# Power_5V.net
KiCad netlist of a schematic drawn in Altium Designer
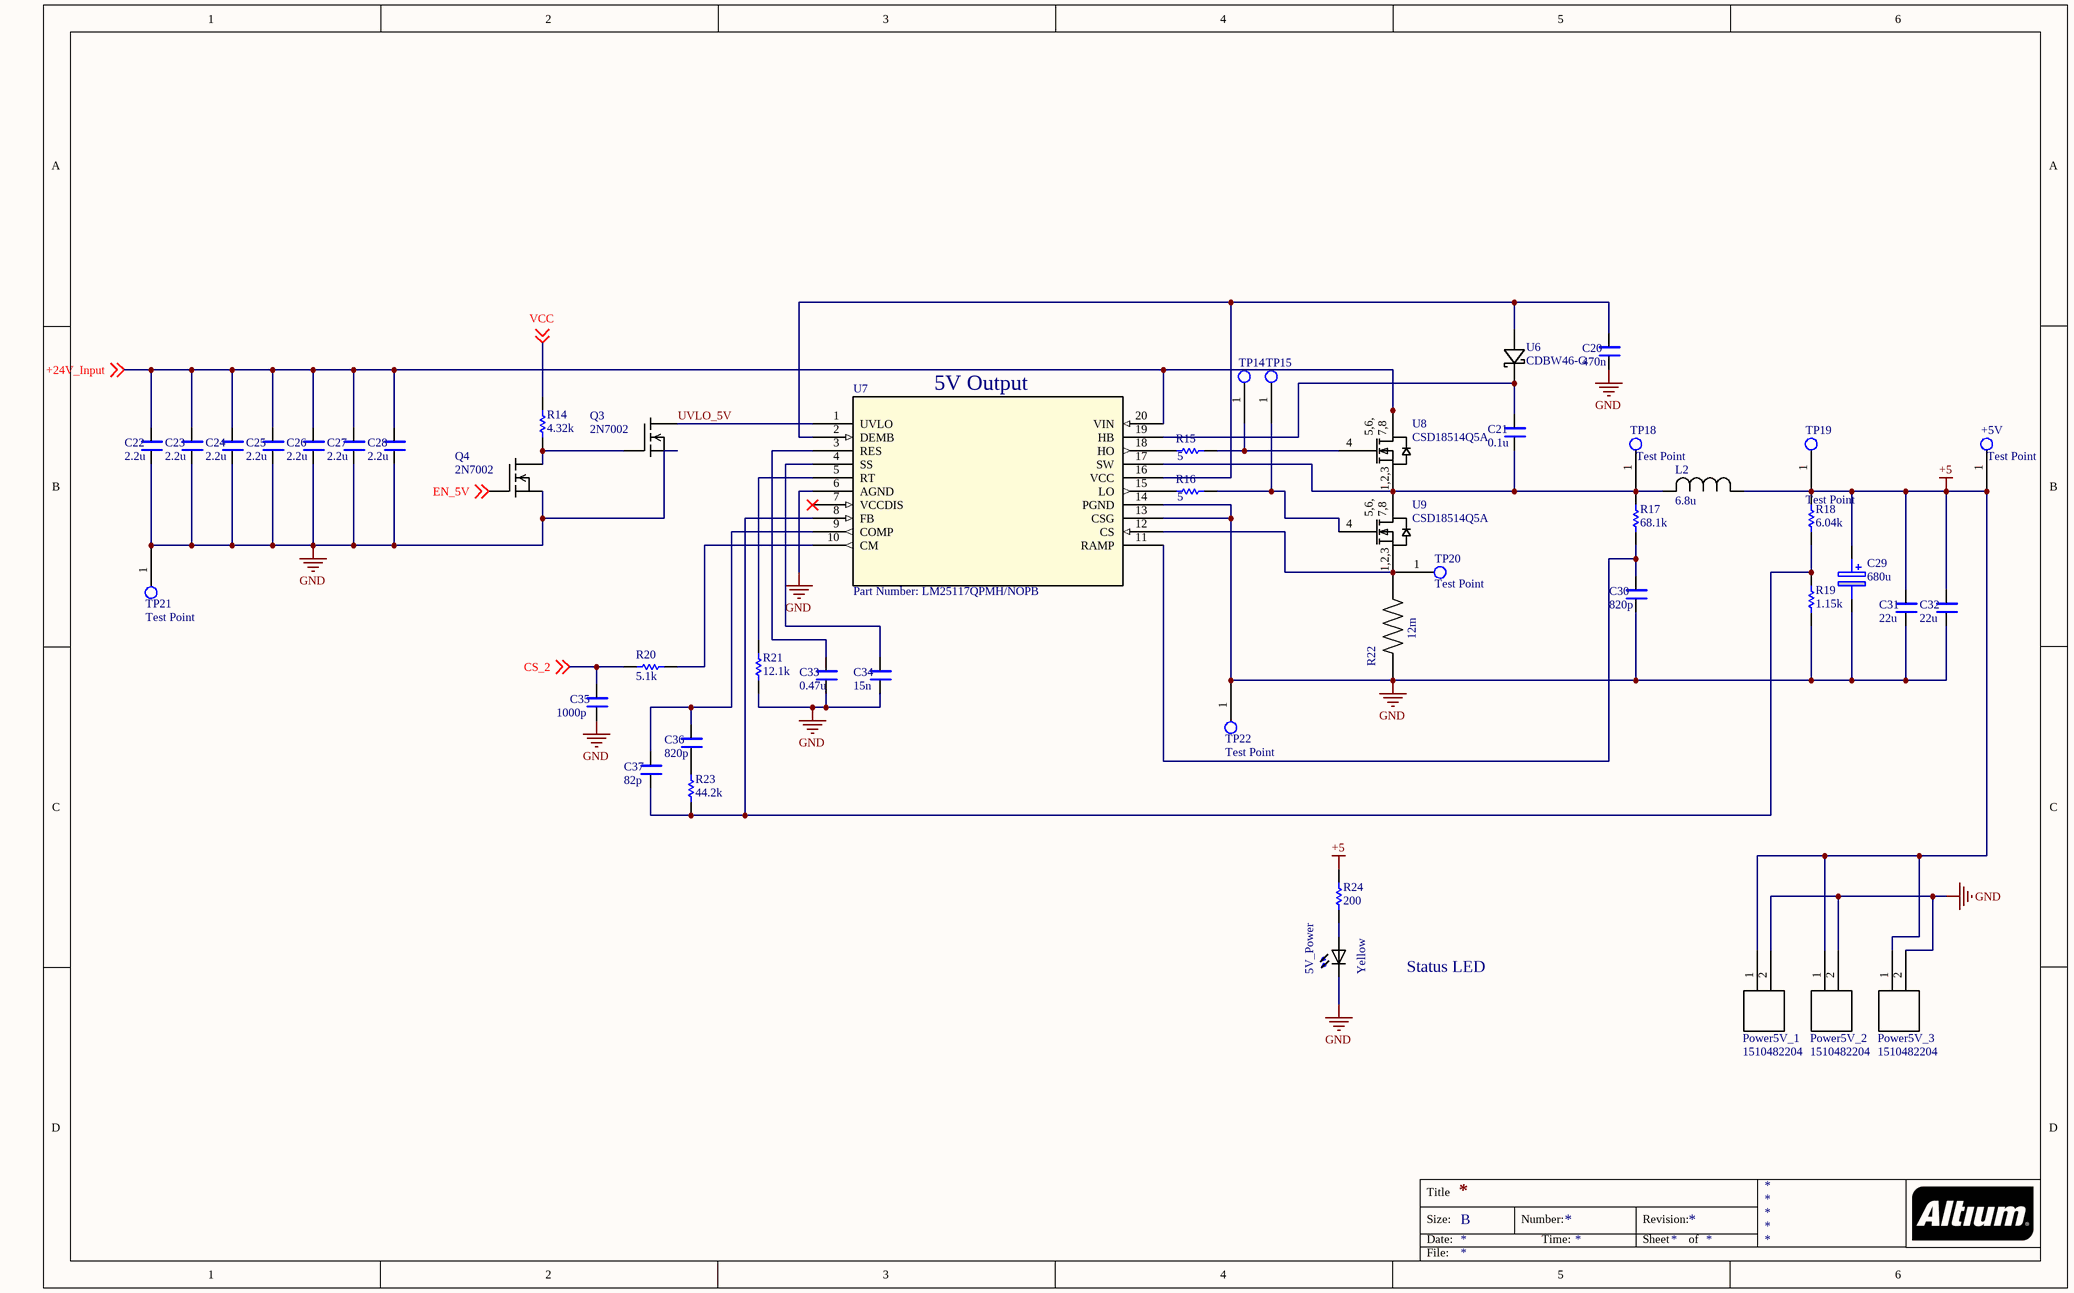
[diagram p0: Power_5V.SchDoc]

(export (version "E")
  (design (tool "Eeschema 10.0.6"))
  (components
    (comp (ref "+5V")
      (value "Test Point")
      (footprint "Test Point Through-hole")
      (libsource (lib "Test Points") (part "Test Point"))
    )
    (comp (ref "5V_Power")
      (value "Yellow")
      (footprint "*DIOC200X125X110_LTST-C171KSKT(Primary)")
      (description "Yellow 2 x 1.25 x 0.8 mm 130Â° Water Clear 50 mcd 2 V LED SMT")
      (fields (field (name "MP") "LTST-C171KSKT") (field (name "DIGI-KEY_PART_NUMBER") "160-1428-1-ND"))
      (libsource (lib "LTST-C171KSKT") (part "LTST-C171KSKT"))
    )
    (comp (ref "C20")
      (value "470n")
      (footprint "*CAPC2012X88N")
      (description "100pF Â±5% 250V Ceramic Capacitor C0G, NP0 0805 _2012 Metric_")
      (fields (field (name "MF") "KEMET") (field (name "DIGI-KEY_PART_NUMBER") "399-15000-1-ND"))
      (libsource (lib "C0805C101JAGAC7800") (part "C0805C101JAGAC7800"))
    )
    (comp (ref "C21")
      (value "0.1u")
      (footprint "*CAPC2012X88N")
      (description "100pF Â±5% 250V Ceramic Capacitor C0G, NP0 0805 _2012 Metric_")
      (fields (field (name "MF") "KEMET") (field (name "DIGI-KEY_PART_NUMBER") "399-15000-1-ND"))
      (libsource (lib "C0805C101JAGAC7800") (part "C0805C101JAGAC7800"))
    )
    (comp (ref "C22")
      (value "2.2u")
      (footprint "*CAPC2012X88N")
      (description "100pF Â±5% 250V Ceramic Capacitor C0G, NP0 0805 _2012 Metric_")
      (fields (field (name "MF") "KEMET") (field (name "DIGI-KEY_PART_NUMBER") "399-15000-1-ND"))
      (libsource (lib "C0805C101JAGAC7800") (part "C0805C101JAGAC7800"))
    )
    (comp (ref "C23")
      (value "2.2u")
      (footprint "*CAPC2012X88N")
      (description "100pF Â±5% 250V Ceramic Capacitor C0G, NP0 0805 _2012 Metric_")
      (fields (field (name "MF") "KEMET") (field (name "DIGI-KEY_PART_NUMBER") "399-15000-1-ND"))
      (libsource (lib "C0805C101JAGAC7800") (part "C0805C101JAGAC7800"))
    )
    (comp (ref "C24")
      (value "2.2u")
      (footprint "*CAPC2012X88N")
      (description "100pF Â±5% 250V Ceramic Capacitor C0G, NP0 0805 _2012 Metric_")
      (fields (field (name "MF") "KEMET") (field (name "DIGI-KEY_PART_NUMBER") "399-15000-1-ND"))
      (libsource (lib "C0805C101JAGAC7800") (part "C0805C101JAGAC7800"))
    )
    (comp (ref "C25")
      (value "2.2u")
      (footprint "*CAPC2012X88N")
      (description "100pF Â±5% 250V Ceramic Capacitor C0G, NP0 0805 _2012 Metric_")
      (fields (field (name "MF") "KEMET") (field (name "DIGI-KEY_PART_NUMBER") "399-15000-1-ND"))
      (libsource (lib "C0805C101JAGAC7800") (part "C0805C101JAGAC7800"))
    )
    (comp (ref "C26")
      (value "2.2u")
      (footprint "*CAPC2012X88N")
      (description "100pF Â±5% 250V Ceramic Capacitor C0G, NP0 0805 _2012 Metric_")
      (fields (field (name "MF") "KEMET") (field (name "DIGI-KEY_PART_NUMBER") "399-15000-1-ND"))
      (libsource (lib "C0805C101JAGAC7800") (part "C0805C101JAGAC7800"))
    )
    (comp (ref "C27")
      (value "2.2u")
      (footprint "*CAPC2012X88N")
      (description "100pF Â±5% 250V Ceramic Capacitor C0G, NP0 0805 _2012 Metric_")
      (fields (field (name "MF") "KEMET") (field (name "DIGI-KEY_PART_NUMBER") "399-15000-1-ND"))
      (libsource (lib "C0805C101JAGAC7800") (part "C0805C101JAGAC7800"))
    )
    (comp (ref "C28")
      (value "2.2u")
      (footprint "*CAPC2012X88N")
      (description "100pF Â±5% 250V Ceramic Capacitor C0G, NP0 0805 _2012 Metric_")
      (fields (field (name "MF") "KEMET") (field (name "DIGI-KEY_PART_NUMBER") "399-15000-1-ND"))
      (libsource (lib "C0805C101JAGAC7800") (part "C0805C101JAGAC7800"))
    )
    (comp (ref "C29")
      (value "680u")
      (footprint "CAPPRD500W65D1000H1800")
      (fields
        (field (name "MANUFACTURER_PART_NUMBER") "EEUFC1V331")
        (field (name "RS PART NUMBER") "1081337")
      )
      (libsource (lib "Power Distribution") (part "EEUFC1V331"))
    )
    (comp (ref "C30")
      (value "820p")
      (footprint "*CAPC2012X88N")
      (description "100pF Â±5% 250V Ceramic Capacitor C0G, NP0 0805 _2012 Metric_")
      (fields (field (name "MF") "KEMET") (field (name "DIGI-KEY_PART_NUMBER") "399-15000-1-ND"))
      (libsource (lib "C0805C101JAGAC7800") (part "C0805C101JAGAC7800"))
    )
    (comp (ref "C31")
      (value "22u")
      (footprint "*CAPC2012X88N")
      (description "100pF Â±5% 250V Ceramic Capacitor C0G, NP0 0805 _2012 Metric_")
      (fields (field (name "MF") "KEMET") (field (name "DIGI-KEY_PART_NUMBER") "399-15000-1-ND"))
      (libsource (lib "C0805C101JAGAC7800") (part "C0805C101JAGAC7800"))
    )
    (comp (ref "C32")
      (value "22u")
      (footprint "*CAPC2012X88N")
      (description "100pF Â±5% 250V Ceramic Capacitor C0G, NP0 0805 _2012 Metric_")
      (fields (field (name "MF") "KEMET") (field (name "DIGI-KEY_PART_NUMBER") "399-15000-1-ND"))
      (libsource (lib "C0805C101JAGAC7800") (part "C0805C101JAGAC7800"))
    )
    (comp (ref "C33")
      (value "0.47u")
      (footprint "*CAPC2012X88N")
      (description "100pF Â±5% 250V Ceramic Capacitor C0G, NP0 0805 _2012 Metric_")
      (fields (field (name "MF") "KEMET") (field (name "DIGI-KEY_PART_NUMBER") "399-15000-1-ND"))
      (libsource (lib "C0805C101JAGAC7800") (part "C0805C101JAGAC7800"))
    )
    (comp (ref "C34")
      (value "15n")
      (footprint "*CAPC2012X88N")
      (description "100pF Â±5% 250V Ceramic Capacitor C0G, NP0 0805 _2012 Metric_")
      (fields (field (name "MF") "KEMET") (field (name "DIGI-KEY_PART_NUMBER") "399-15000-1-ND"))
      (libsource (lib "C0805C101JAGAC7800") (part "C0805C101JAGAC7800"))
    )
    (comp (ref "C35")
      (value "1000p")
      (footprint "*CAPC2012X88N")
      (description "100pF Â±5% 250V Ceramic Capacitor C0G, NP0 0805 _2012 Metric_")
      (fields (field (name "MF") "KEMET") (field (name "DIGI-KEY_PART_NUMBER") "399-15000-1-ND"))
      (libsource (lib "C0805C101JAGAC7800") (part "C0805C101JAGAC7800"))
    )
    (comp (ref "C36")
      (value "820p")
      (footprint "*CAPC2012X88N")
      (description "100pF Â±5% 250V Ceramic Capacitor C0G, NP0 0805 _2012 Metric_")
      (fields (field (name "MF") "KEMET") (field (name "DIGI-KEY_PART_NUMBER") "399-15000-1-ND"))
      (libsource (lib "C0805C101JAGAC7800") (part "C0805C101JAGAC7800"))
    )
    (comp (ref "C37")
      (value "82p")
      (footprint "*CAPC2012X88N")
      (description "100pF Â±5% 250V Ceramic Capacitor C0G, NP0 0805 _2012 Metric_")
      (fields (field (name "MF") "KEMET") (field (name "DIGI-KEY_PART_NUMBER") "399-15000-1-ND"))
      (libsource (lib "C0805C101JAGAC7800") (part "C0805C101JAGAC7800"))
    )
    (comp (ref "L2")
      (value "6.8u")
      (footprint "IND_BOURNS_SRP12")
      (description "No Description Available")
      (fields
        (field (name "MANUFACTURER_PART_NUMBER") "SRP1270-6R8M")
        (field (name "COPYRIGHT") "Copyright (C) 2018 Accelerated Designs. All rights reserved")
      )
      (libsource (lib "Inductor") (part "SRP1270-6R8M"))
    )
    (comp (ref "Power5V_1")
      (value "1510482204")
      (footprint "1510482204")
      (description "Molex 6.5MM 2 pin connector, used for power connections. P/N 1510482204 and similar models.")
      (libsource (lib "Power Distribution") (part "1510482204"))
    )
    (comp (ref "Power5V_2")
      (value "1510482204")
      (footprint "1510482204")
      (description "Molex 6.5MM 2 pin connector, used for power connections. P/N 1510482204 and similar models.")
      (libsource (lib "Power Distribution") (part "1510482204"))
    )
    (comp (ref "Power5V_3")
      (value "1510482204")
      (footprint "1510482204")
      (description "Molex 6.5MM 2 pin connector, used for power connections. P/N 1510482204 and similar models.")
      (libsource (lib "Power Distribution") (part "1510482204"))
    )
    (comp (ref "Q3")
      (value "2N7002")
      (footprint "*SOT23")
      (description "Trans MOSFET N-CH 60V 0.115A 3-Pin SOT-23 T/R")
      (fields (field (name "MF") "ON Semiconductor"))
      (libsource (lib "2N7002") (part "2N7002"))
    )
    (comp (ref "Q4")
      (value "2N7002")
      (footprint "*SOT23")
      (description "Trans MOSFET N-CH 60V 0.115A 3-Pin SOT-23 T/R")
      (fields (field (name "MF") "ON Semiconductor"))
      (libsource (lib "2N7002") (part "2N7002"))
    )
    (comp (ref "R14")
      (value "4.32k")
      (footprint "RESC0805(2012)_M")
      (description "8M06 0.125W 1% 0805 (2012 Metric)  SMD")
      (fields (field (name "POWER") "0.125 W") (field (name "TOLERANCE") "1 %"))
      (libsource (lib "Altium Content Vault") (part "RES"))
    )
    (comp (ref "R15")
      (value "5")
      (footprint "AXIAL-0.3")
      (description "120R 0.125W 5% 0805 (2012 Metric)  SMD")
      (fields (field (name "TOLERANCE") "5 %") (field (name "POWER") "0.125 W"))
      (libsource (lib "Power Distribution") (part "120R 5% 0805"))
    )
    (comp (ref "R16")
      (value "5")
      (footprint "AXIAL-0.3")
      (description "120R 0.125W 5% 0805 (2012 Metric)  SMD")
      (fields (field (name "TOLERANCE") "5 %") (field (name "POWER") "0.125 W"))
      (libsource (lib "Power Distribution") (part "120R 5% 0805"))
    )
    (comp (ref "R17")
      (value "68.1k")
      (footprint "RESC0805(2012)_M")
      (description "8M06 0.125W 1% 0805 (2012 Metric)  SMD")
      (fields (field (name "POWER") "0.125 W") (field (name "TOLERANCE") "1 %"))
      (libsource (lib "Altium Content Vault") (part "RES"))
    )
    (comp (ref "R18")
      (value "6.04k")
      (footprint "RESC0805(2012)_M")
      (description "8M06 0.125W 1% 0805 (2012 Metric)  SMD")
      (fields (field (name "POWER") "0.125 W") (field (name "TOLERANCE") "1 %"))
      (libsource (lib "Altium Content Vault") (part "RES"))
    )
    (comp (ref "R19")
      (value "1.15k")
      (footprint "RESC0805(2012)_M")
      (description "8M06 0.125W 1% 0805 (2012 Metric)  SMD")
      (fields (field (name "POWER") "0.125 W") (field (name "TOLERANCE") "1 %"))
      (libsource (lib "Altium Content Vault") (part "RES"))
    )
    (comp (ref "R20")
      (value "5.1k")
      (footprint "RESC0805(2012)_M")
      (description "8M06 0.125W 1% 0805 (2012 Metric)  SMD")
      (fields (field (name "POWER") "0.125 W") (field (name "TOLERANCE") "1 %"))
      (libsource (lib "Altium Content Vault") (part "RES"))
    )
    (comp (ref "R21")
      (value "12.1k")
      (footprint "RESC0805(2012)_M")
      (description "8M06 0.125W 1% 0805 (2012 Metric)  SMD")
      (fields (field (name "POWER") "0.125 W") (field (name "TOLERANCE") "1 %"))
      (libsource (lib "Altium Content Vault") (part "RES"))
    )
    (comp (ref "R22")
      (value "12m")
      (footprint "*RESC6432X110N")
      (description "Res Thick Film 2512 0.012 Ohm 1% 1W Pad SMD Automotive T/R")
      (fields (field (name "MP") "ERJ-M1WSF12MU") (field (name "DIGI-KEY_PART_NUMBER") "P12MCT-ND"))
      (libsource (lib "ERJ-M1WSF12MU") (part "ERJ-M1WSF12MU"))
    )
    (comp (ref "R23")
      (value "44.2k")
      (footprint "RESC0805(2012)_M")
      (description "8M06 0.125W 1% 0805 (2012 Metric)  SMD")
      (fields (field (name "POWER") "0.125 W") (field (name "TOLERANCE") "1 %"))
      (libsource (lib "Altium Content Vault") (part "RES"))
    )
    (comp (ref "R24")
      (value "200")
      (footprint "RESC0805(2012)_M")
      (description "8M06 0.125W 1% 0805 (2012 Metric)  SMD")
      (fields (field (name "POWER") "0.125 W") (field (name "TOLERANCE") "1 %"))
      (libsource (lib "Altium Content Vault") (part "RES"))
    )
    (comp (ref "TP14")
      (value "~")
      (footprint "Test Point Through-hole")
      (libsource (lib "Test Points") (part "Test Point"))
    )
    (comp (ref "TP15")
      (value "~")
      (footprint "Test Point Through-hole")
      (libsource (lib "Test Points") (part "Test Point"))
    )
    (comp (ref "TP18")
      (value "Test Point")
      (footprint "Test Point Through-hole")
      (libsource (lib "Test Points") (part "Test Point"))
    )
    (comp (ref "TP19")
      (value "Test Point")
      (footprint "Test Point Through-hole")
      (libsource (lib "Test Points") (part "Test Point"))
    )
    (comp (ref "TP20")
      (value "Test Point")
      (footprint "Test Point Through-hole")
      (libsource (lib "Test Points") (part "Test Point"))
    )
    (comp (ref "TP21")
      (value "Test Point")
      (footprint "Test Point Through-hole")
      (libsource (lib "Test Points") (part "Test Point"))
    )
    (comp (ref "TP22")
      (value "Test Point")
      (footprint "Test Point Through-hole")
      (libsource (lib "Test Points") (part "Test Point"))
    )
    (comp (ref "U6")
      (value "CDBW46-G")
      (footprint "CDBW")
      (description "No Description Available")
      (fields (field (name "COPYRIGHT") "Copyright (C) 2018 Accelerated Designs. All rights reserved"))
      (libsource (lib "DIODE SCHOTTKY 100V 150MA") (part "CDBW46-G"))
    )
    (comp (ref "U7")
      (value "Part Number: LM25117QPMH/NOPB")
      (footprint "MXA20A")
      (description "No Description Available")
      (fields
        (field (name "MANUFACTURER") "Texas Instruments")
        (field (name "MANUFACTURER_PART_NUMBER") "LM25117QPMH/NOPB")
        (field (name "COPYRIGHT") "Copyright (C) 2018 Accelerated Designs. All rights reserved")
      )
      (libsource (lib "2019-11-16_22-35-15") (part "LM25117QPMH/NOPB"))
    )
    (comp (ref "U8")
      (value "CSD18514Q5A")
      (footprint "DQJ0008A")
      (description "No Description Available")
      (fields (field (name "COPYRIGHT") "Copyright (C) 2018 Accelerated Designs. All rights reserved"))
      (libsource (lib "ul_CSD18514Q5A") (part "CSD18514Q5A"))
    )
    (comp (ref "U9")
      (value "CSD18514Q5A")
      (footprint "DQJ0008A")
      (description "No Description Available")
      (fields (field (name "COPYRIGHT") "Copyright (C) 2018 Accelerated Designs. All rights reserved"))
      (libsource (lib "ul_CSD18514Q5A") (part "CSD18514Q5A"))
    )
  )
  (nets
    (net (code "1") (name "+5") (class "Default")
      (node (ref "+5V") (pin "1") (pinfunction "1_1") (pintype "passive"))
      (node (ref "C29") (pin "1") (pinfunction "+_1") (pintype "passive"))
      (node (ref "C31") (pin "2") (pinfunction "2_2") (pintype "passive"))
      (node (ref "C32") (pin "2") (pinfunction "2_2") (pintype "passive"))
      (node (ref "L2") (pin "1") (pinfunction "1_1") (pintype "passive"))
      (node (ref "Power5V_1") (pin "1") (pintype "passive"))
      (node (ref "Power5V_2") (pin "1") (pintype "passive"))
      (node (ref "Power5V_3") (pin "1") (pintype "passive"))
      (node (ref "R18") (pin "2") (pinfunction "2_2") (pintype "passive"))
      (node (ref "R24") (pin "2") (pinfunction "2_2") (pintype "passive"))
      (node (ref "TP19") (pin "1") (pinfunction "1_1") (pintype "passive"))
    )
    (net (code "2") (name "+24V_Input") (class "Default")
      (node (ref "C22") (pin "2") (pinfunction "2_2") (pintype "passive"))
      (node (ref "C23") (pin "2") (pinfunction "2_2") (pintype "passive"))
      (node (ref "C24") (pin "2") (pinfunction "2_2") (pintype "passive"))
      (node (ref "C25") (pin "2") (pinfunction "2_2") (pintype "passive"))
      (node (ref "C26") (pin "2") (pinfunction "2_2") (pintype "passive"))
      (node (ref "C27") (pin "2") (pinfunction "2_2") (pintype "passive"))
      (node (ref "C28") (pin "2") (pinfunction "2_2") (pintype "passive"))
      (node (ref "U7") (pin "20") (pinfunction "VIN_20") (pintype "input"))
      (node (ref "U8") (pin "5") (pinfunction "D_5") (pintype "passive"))
      (node (ref "U8") (pin "6") (pinfunction "D_6") (pintype "passive"))
      (node (ref "U8") (pin "7") (pinfunction "D_7") (pintype "passive"))
      (node (ref "U8") (pin "8") (pinfunction "D_8") (pintype "passive"))
    )
    (net (code "3") (name "/UVLO_5V") (class "Default")
      (node (ref "Q3") (pin "3") (pinfunction "D_3") (pintype "passive"))
      (node (ref "U7") (pin "1") (pinfunction "UVLO_1") (pintype "passive"))
    )
    (net (code "4") (name "CS_2") (class "Default")
      (node (ref "C35") (pin "2") (pinfunction "2_2") (pintype "passive"))
      (node (ref "R20") (pin "2") (pinfunction "2_2") (pintype "passive"))
    )
    (net (code "5") (name "EN_5V") (class "Default")
      (node (ref "Q4") (pin "1") (pinfunction "G_1") (pintype "passive"))
    )
    (net (code "6") (name "GND") (class "Default")
      (node (ref "5V_Power") (pin "NEG") (pinfunction "NEG_NEG") (pintype "passive"))
      (node (ref "C20") (pin "1") (pinfunction "1_1") (pintype "passive"))
      (node (ref "C22") (pin "1") (pinfunction "1_1") (pintype "passive"))
      (node (ref "C23") (pin "1") (pinfunction "1_1") (pintype "passive"))
      (node (ref "C24") (pin "1") (pinfunction "1_1") (pintype "passive"))
      (node (ref "C25") (pin "1") (pinfunction "1_1") (pintype "passive"))
      (node (ref "C26") (pin "1") (pinfunction "1_1") (pintype "passive"))
      (node (ref "C27") (pin "1") (pinfunction "1_1") (pintype "passive"))
      (node (ref "C28") (pin "1") (pinfunction "1_1") (pintype "passive"))
      (node (ref "C29") (pin "2") (pinfunction "-_2") (pintype "passive"))
      (node (ref "C30") (pin "1") (pinfunction "1_1") (pintype "passive"))
      (node (ref "C31") (pin "1") (pinfunction "1_1") (pintype "passive"))
      (node (ref "C32") (pin "1") (pinfunction "1_1") (pintype "passive"))
      (node (ref "C33") (pin "1") (pinfunction "1_1") (pintype "passive"))
      (node (ref "C34") (pin "1") (pinfunction "1_1") (pintype "passive"))
      (node (ref "C35") (pin "1") (pinfunction "1_1") (pintype "passive"))
      (node (ref "Power5V_1") (pin "2") (pintype "passive"))
      (node (ref "Power5V_2") (pin "2") (pintype "passive"))
      (node (ref "Power5V_3") (pin "2") (pintype "passive"))
      (node (ref "Q3") (pin "2") (pinfunction "S_2") (pintype "passive"))
      (node (ref "Q4") (pin "2") (pinfunction "S_2") (pintype "passive"))
      (node (ref "R19") (pin "1") (pinfunction "1_1") (pintype "passive"))
      (node (ref "R21") (pin "1") (pinfunction "1_1") (pintype "passive"))
      (node (ref "R22") (pin "1") (pinfunction "1_1") (pintype "passive"))
      (node (ref "TP21") (pin "1") (pinfunction "1_1") (pintype "passive"))
      (node (ref "TP22") (pin "1") (pinfunction "1_1") (pintype "passive"))
      (node (ref "U7") (pin "13") (pinfunction "CSG_13") (pintype "passive"))
      (node (ref "U7") (pin "14") (pinfunction "PGND_14") (pintype "power_in"))
      (node (ref "U7") (pin "6") (pinfunction "AGND_6") (pintype "power_in"))
    )
    (net (code "7") (name "Net-(5V_Power-PadPOS)") (class "Default")
      (node (ref "5V_Power") (pin "POS") (pinfunction "POS_POS") (pintype "passive"))
      (node (ref "R24") (pin "1") (pinfunction "1_1") (pintype "passive"))
    )
    (net (code "8") (name "Net-(C36-Pad1)") (class "Default")
      (node (ref "C36") (pin "1") (pinfunction "1_1") (pintype "passive"))
      (node (ref "R23") (pin "2") (pinfunction "2_2") (pintype "passive"))
    )
    (net (code "9") (name "Net-(Q3-G)") (class "Default")
      (node (ref "Q3") (pin "1") (pinfunction "G_1") (pintype "passive"))
      (node (ref "Q4") (pin "3") (pinfunction "D_3") (pintype "passive"))
      (node (ref "R14") (pin "1") (pinfunction "1_1") (pintype "passive"))
    )
    (net (code "10") (name "Net-(U7-CM)") (class "Default")
      (node (ref "R20") (pin "1") (pinfunction "1_1") (pintype "passive"))
      (node (ref "U7") (pin "10") (pinfunction "CM_10") (pintype "output"))
    )
    (net (code "11") (name "Net-(U7-COMP)") (class "Default")
      (node (ref "C36") (pin "2") (pinfunction "2_2") (pintype "passive"))
      (node (ref "C37") (pin "2") (pinfunction "2_2") (pintype "passive"))
      (node (ref "U7") (pin "9") (pinfunction "COMP_9") (pintype "output"))
    )
    (net (code "12") (name "Net-(U7-CS)") (class "Default")
      (node (ref "R22") (pin "2") (pinfunction "2_2") (pintype "passive"))
      (node (ref "TP20") (pin "1") (pinfunction "1_1") (pintype "passive"))
      (node (ref "U7") (pin "12") (pinfunction "CS_12") (pintype "input"))
      (node (ref "U9") (pin "1") (pinfunction "S_1") (pintype "passive"))
      (node (ref "U9") (pin "2") (pinfunction "S_2") (pintype "passive"))
      (node (ref "U9") (pin "3") (pinfunction "S_3") (pintype "passive"))
    )
    (net (code "13") (name "Net-(U7-DEMB)") (class "Default")
      (node (ref "C20") (pin "2") (pinfunction "2_2") (pintype "passive"))
      (node (ref "U6") (pin "2") (pinfunction "2_2") (pintype "passive"))
      (node (ref "U7") (pin "16") (pinfunction "VCC_16") (pintype "power_in"))
      (node (ref "U7") (pin "2") (pinfunction "DEMB_2") (pintype "input"))
    )
    (net (code "14") (name "Net-(U7-FB)") (class "Default")
      (node (ref "C37") (pin "1") (pinfunction "1_1") (pintype "passive"))
      (node (ref "R18") (pin "1") (pinfunction "1_1") (pintype "passive"))
      (node (ref "R19") (pin "2") (pinfunction "2_2") (pintype "passive"))
      (node (ref "R23") (pin "1") (pinfunction "1_1") (pintype "passive"))
      (node (ref "U7") (pin "8") (pinfunction "FB_8") (pintype "input"))
    )
    (net (code "15") (name "Net-(U7-HB)") (class "Default")
      (node (ref "C21") (pin "2") (pinfunction "2_2") (pintype "passive"))
      (node (ref "U6") (pin "1") (pinfunction "1_1") (pintype "passive"))
      (node (ref "U7") (pin "19") (pinfunction "HB_19") (pintype "passive"))
    )
    (net (code "16") (name "Net-(U7-HO)") (class "Default")
      (node (ref "R15") (pin "1") (pinfunction "1_1") (pintype "passive"))
      (node (ref "U7") (pin "18") (pinfunction "HO_18") (pintype "output"))
    )
    (net (code "17") (name "Net-(U7-LO)") (class "Default")
      (node (ref "R16") (pin "1") (pinfunction "1_1") (pintype "passive"))
      (node (ref "U7") (pin "15") (pinfunction "LO_15") (pintype "output"))
    )
    (net (code "18") (name "Net-(U7-RAMP)") (class "Default")
      (node (ref "C30") (pin "2") (pinfunction "2_2") (pintype "passive"))
      (node (ref "R17") (pin "1") (pinfunction "1_1") (pintype "passive"))
      (node (ref "U7") (pin "11") (pinfunction "RAMP_11") (pintype "passive"))
    )
    (net (code "19") (name "Net-(U7-RES)") (class "Default")
      (node (ref "C33") (pin "2") (pinfunction "2_2") (pintype "passive"))
      (node (ref "U7") (pin "3") (pinfunction "RES_3") (pintype "passive"))
    )
    (net (code "20") (name "Net-(U7-RT)") (class "Default")
      (node (ref "R21") (pin "2") (pinfunction "2_2") (pintype "passive"))
      (node (ref "U7") (pin "5") (pinfunction "RT_5") (pintype "passive"))
    )
    (net (code "21") (name "Net-(U7-SS)") (class "Default")
      (node (ref "C34") (pin "2") (pinfunction "2_2") (pintype "passive"))
      (node (ref "U7") (pin "4") (pinfunction "SS_4") (pintype "passive"))
    )
    (net (code "22") (name "Net-(U7-SW)") (class "Default")
      (node (ref "C21") (pin "1") (pinfunction "1_1") (pintype "passive"))
      (node (ref "L2") (pin "2") (pinfunction "2_2") (pintype "passive"))
      (node (ref "R17") (pin "2") (pinfunction "2_2") (pintype "passive"))
      (node (ref "TP18") (pin "1") (pinfunction "1_1") (pintype "passive"))
      (node (ref "U7") (pin "17") (pinfunction "SW_17") (pintype "passive"))
      (node (ref "U8") (pin "1") (pinfunction "S_1") (pintype "passive"))
      (node (ref "U8") (pin "2") (pinfunction "S_2") (pintype "passive"))
      (node (ref "U8") (pin "3") (pinfunction "S_3") (pintype "passive"))
      (node (ref "U9") (pin "5") (pinfunction "D_5") (pintype "passive"))
      (node (ref "U9") (pin "6") (pinfunction "D_6") (pintype "passive"))
      (node (ref "U9") (pin "7") (pinfunction "D_7") (pintype "passive"))
      (node (ref "U9") (pin "8") (pinfunction "D_8") (pintype "passive"))
    )
    (net (code "23") (name "Net-(U8-G)") (class "Default")
      (node (ref "R15") (pin "2") (pinfunction "2_2") (pintype "passive"))
      (node (ref "TP14") (pin "1") (pinfunction "1_1") (pintype "passive"))
      (node (ref "U8") (pin "4") (pinfunction "G_4") (pintype "passive"))
    )
    (net (code "24") (name "Net-(U9-G)") (class "Default")
      (node (ref "R16") (pin "2") (pinfunction "2_2") (pintype "passive"))
      (node (ref "TP15") (pin "1") (pinfunction "1_1") (pintype "passive"))
      (node (ref "U9") (pin "4") (pinfunction "G_4") (pintype "passive"))
    )
    (net (code "25") (name "VCC") (class "Default")
      (node (ref "R14") (pin "2") (pinfunction "2_2") (pintype "passive"))
    )
    (net (code "26") (name "unconnected-(U7-VCCDIS-Pad7)") (class "Default")
      (node (ref "U7") (pin "7") (pinfunction "VCCDIS_7") (pintype "input+no_connect"))
    )
  )
)
